# Relay_Board.net
KiCad netlist of a schematic drawn in EAGLE
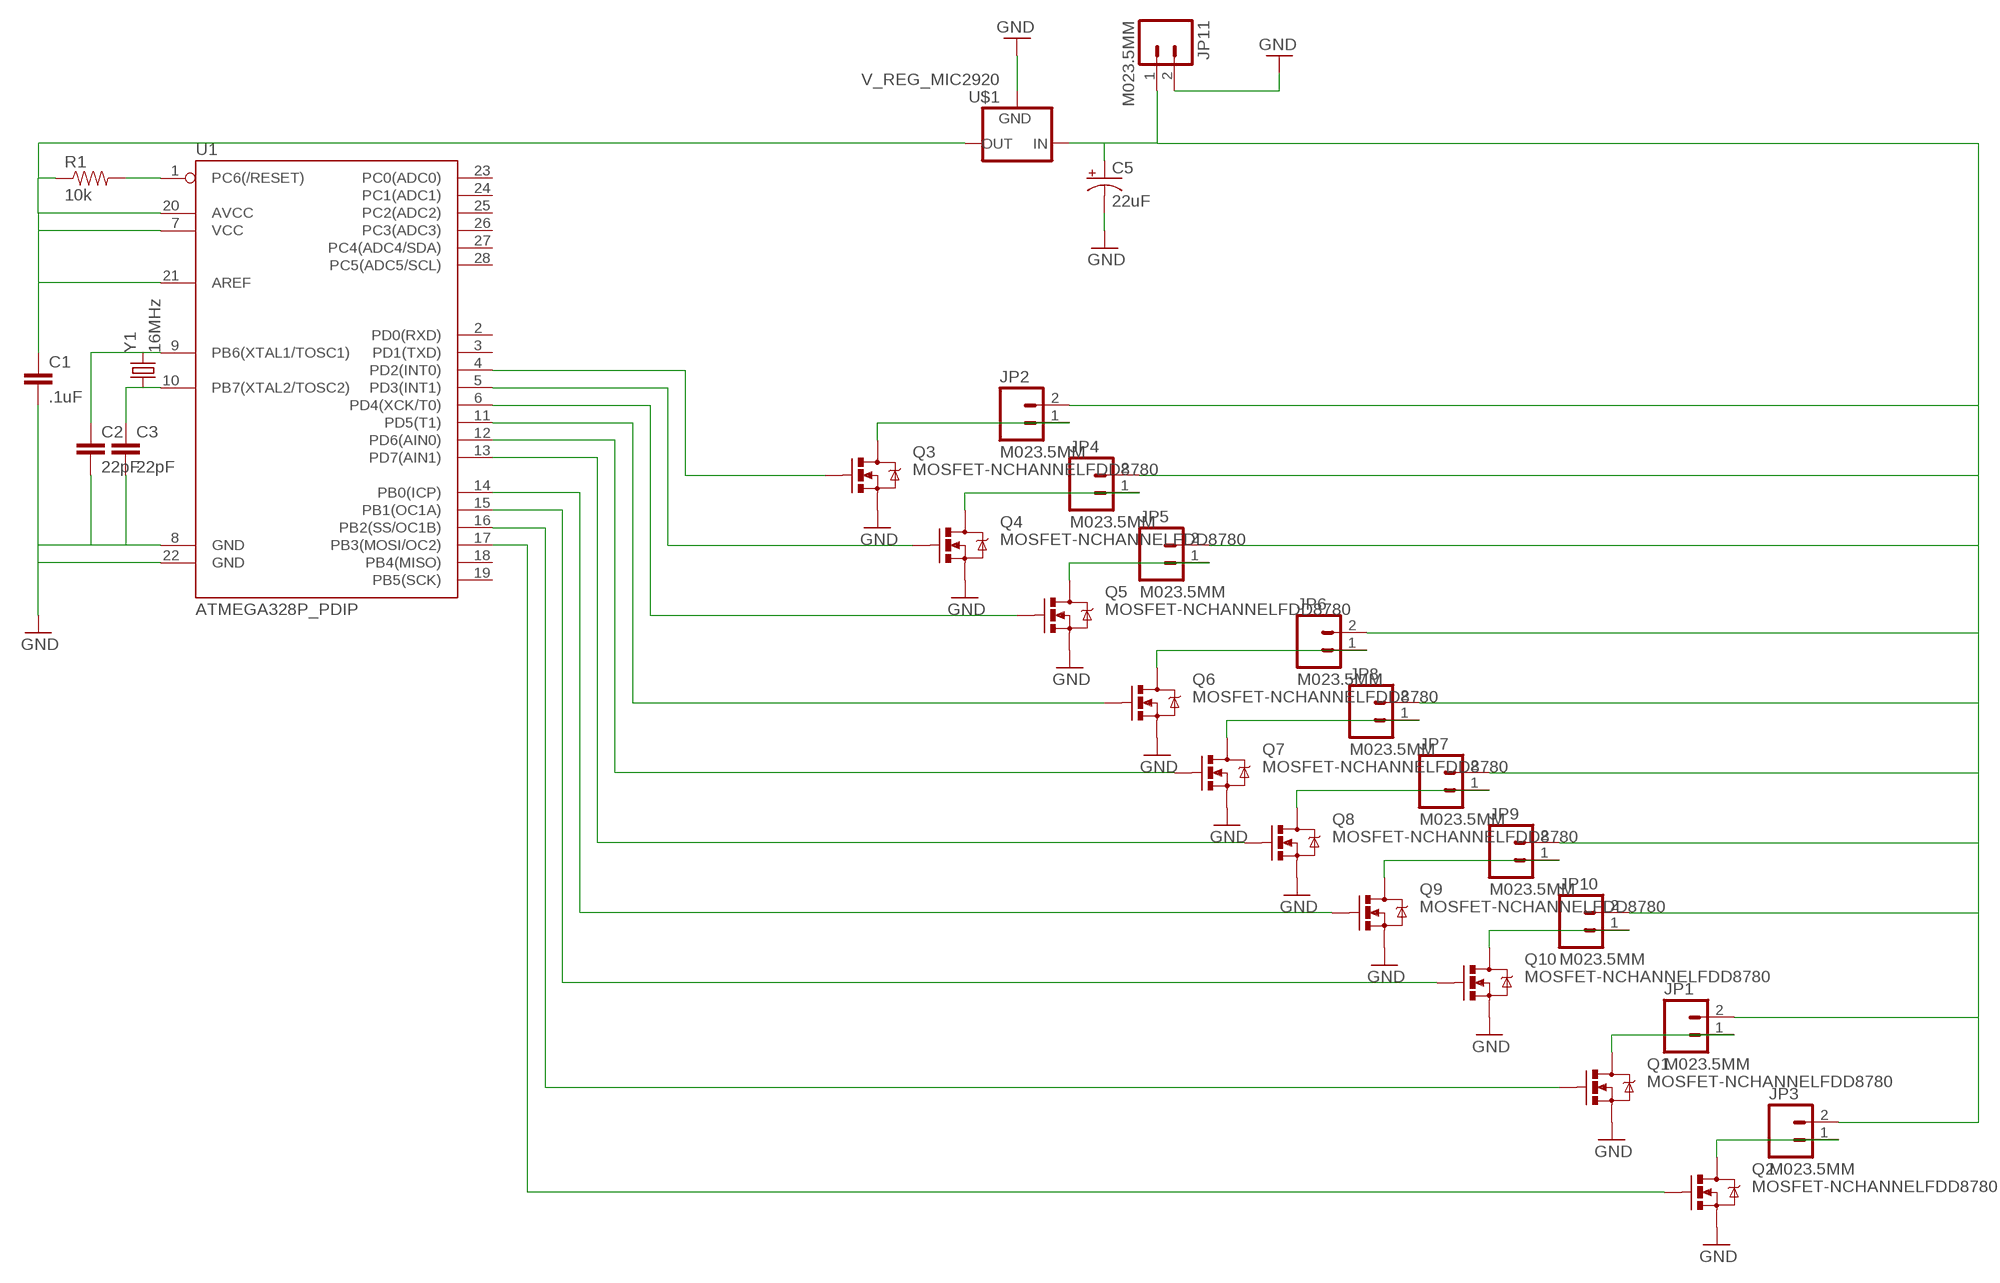
[diagram p0: schematic, sheet 1]

(export (version "E")
  (design (tool "Eeschema 10.0.6"))
  (components
    (comp (ref "C1")
      (value ".1uF")
      (footprint "eagle-import:1206")
      (libsource (lib "eagle-import") (part "CAP1206"))
    )
    (comp (ref "C2")
      (value "22pF")
      (footprint "eagle-import:1206")
      (libsource (lib "eagle-import") (part "CAP1206"))
    )
    (comp (ref "C3")
      (value "22pF")
      (footprint "eagle-import:1206")
      (libsource (lib "eagle-import") (part "CAP1206"))
    )
    (comp (ref "C5")
      (value "22uF")
      (footprint "eagle-import:PANASONIC_C")
      (libsource (lib "eagle-import") (part "CAP_POLC"))
    )
    (comp (ref "JP1")
      (value "M023.5MM")
      (footprint "eagle-import:SCREWTERMINAL-3.5MM-2")
      (libsource (lib "eagle-import") (part "M023.5MM"))
    )
    (comp (ref "JP2")
      (value "M023.5MM")
      (footprint "eagle-import:SCREWTERMINAL-3.5MM-2")
      (libsource (lib "eagle-import") (part "M023.5MM"))
    )
    (comp (ref "JP3")
      (value "M023.5MM")
      (footprint "eagle-import:SCREWTERMINAL-3.5MM-2")
      (libsource (lib "eagle-import") (part "M023.5MM"))
    )
    (comp (ref "JP4")
      (value "M023.5MM")
      (footprint "eagle-import:SCREWTERMINAL-3.5MM-2")
      (libsource (lib "eagle-import") (part "M023.5MM"))
    )
    (comp (ref "JP5")
      (value "M023.5MM")
      (footprint "eagle-import:SCREWTERMINAL-3.5MM-2")
      (libsource (lib "eagle-import") (part "M023.5MM"))
    )
    (comp (ref "JP6")
      (value "M023.5MM")
      (footprint "eagle-import:SCREWTERMINAL-3.5MM-2")
      (libsource (lib "eagle-import") (part "M023.5MM"))
    )
    (comp (ref "JP7")
      (value "M023.5MM")
      (footprint "eagle-import:SCREWTERMINAL-3.5MM-2")
      (libsource (lib "eagle-import") (part "M023.5MM"))
    )
    (comp (ref "JP8")
      (value "M023.5MM")
      (footprint "eagle-import:SCREWTERMINAL-3.5MM-2")
      (libsource (lib "eagle-import") (part "M023.5MM"))
    )
    (comp (ref "JP9")
      (value "M023.5MM")
      (footprint "eagle-import:SCREWTERMINAL-3.5MM-2")
      (libsource (lib "eagle-import") (part "M023.5MM"))
    )
    (comp (ref "JP10")
      (value "M023.5MM")
      (footprint "eagle-import:SCREWTERMINAL-3.5MM-2")
      (libsource (lib "eagle-import") (part "M023.5MM"))
    )
    (comp (ref "JP11")
      (value "M023.5MM")
      (footprint "eagle-import:SCREWTERMINAL-3.5MM-2")
      (libsource (lib "eagle-import") (part "M023.5MM"))
    )
    (comp (ref "Q1")
      (value "MOSFET-NCHANNELFDD8780")
      (footprint "eagle-import:DPAK")
      (libsource (lib "eagle-import") (part "MOSFET-NCHANNELFDD8780"))
    )
    (comp (ref "Q2")
      (value "MOSFET-NCHANNELFDD8780")
      (footprint "eagle-import:DPAK")
      (libsource (lib "eagle-import") (part "MOSFET-NCHANNELFDD8780"))
    )
    (comp (ref "Q3")
      (value "MOSFET-NCHANNELFDD8780")
      (footprint "eagle-import:DPAK")
      (libsource (lib "eagle-import") (part "MOSFET-NCHANNELFDD8780"))
    )
    (comp (ref "Q4")
      (value "MOSFET-NCHANNELFDD8780")
      (footprint "eagle-import:DPAK")
      (libsource (lib "eagle-import") (part "MOSFET-NCHANNELFDD8780"))
    )
    (comp (ref "Q5")
      (value "MOSFET-NCHANNELFDD8780")
      (footprint "eagle-import:DPAK")
      (libsource (lib "eagle-import") (part "MOSFET-NCHANNELFDD8780"))
    )
    (comp (ref "Q6")
      (value "MOSFET-NCHANNELFDD8780")
      (footprint "eagle-import:DPAK")
      (libsource (lib "eagle-import") (part "MOSFET-NCHANNELFDD8780"))
    )
    (comp (ref "Q7")
      (value "MOSFET-NCHANNELFDD8780")
      (footprint "eagle-import:DPAK")
      (libsource (lib "eagle-import") (part "MOSFET-NCHANNELFDD8780"))
    )
    (comp (ref "Q8")
      (value "MOSFET-NCHANNELFDD8780")
      (footprint "eagle-import:DPAK")
      (libsource (lib "eagle-import") (part "MOSFET-NCHANNELFDD8780"))
    )
    (comp (ref "Q9")
      (value "MOSFET-NCHANNELFDD8780")
      (footprint "eagle-import:DPAK")
      (libsource (lib "eagle-import") (part "MOSFET-NCHANNELFDD8780"))
    )
    (comp (ref "Q10")
      (value "MOSFET-NCHANNELFDD8780")
      (footprint "eagle-import:DPAK")
      (libsource (lib "eagle-import") (part "MOSFET-NCHANNELFDD8780"))
    )
    (comp (ref "R1")
      (value "10k")
      (footprint "eagle-import:1206")
      (libsource (lib "eagle-import") (part "RESISTOR1206"))
    )
    (comp (ref "U$1")
      (value "V_REG_MIC2920")
      (footprint "eagle-import:SOT223")
      (libsource (lib "eagle-import") (part "V_REG_MIC2920"))
    )
    (comp (ref "U1")
      (value "ATMEGA328P_PDIP")
      (footprint "eagle-import:DIL28-3")
      (libsource (lib "eagle-import") (part "ATMEGA328P_PDIP"))
    )
    (comp (ref "Y1")
      (value "16MHz")
      (footprint "eagle-import:CRYSTAL-SMD-5X3")
      (libsource (lib "eagle-import") (part "CRYSTAL5X3"))
    )
  )
  (nets
    (net (code "1") (name "GND") (class "Default")
      (node (ref "C1") (pin "2") (pinfunction "2_2") (pintype "passive"))
      (node (ref "C2") (pin "2") (pinfunction "2_2") (pintype "passive"))
      (node (ref "C3") (pin "2") (pinfunction "2_2") (pintype "passive"))
      (node (ref "C5") (pin "-") (pinfunction "-_-") (pintype "passive"))
      (node (ref "JP11") (pin "2") (pinfunction "2_2") (pintype "passive"))
      (node (ref "Q1") (pin "3") (pinfunction "S_3") (pintype "passive"))
      (node (ref "Q10") (pin "3") (pinfunction "S_3") (pintype "passive"))
      (node (ref "Q2") (pin "3") (pinfunction "S_3") (pintype "passive"))
      (node (ref "Q3") (pin "3") (pinfunction "S_3") (pintype "passive"))
      (node (ref "Q4") (pin "3") (pinfunction "S_3") (pintype "passive"))
      (node (ref "Q5") (pin "3") (pinfunction "S_3") (pintype "passive"))
      (node (ref "Q6") (pin "3") (pinfunction "S_3") (pintype "passive"))
      (node (ref "Q7") (pin "3") (pinfunction "S_3") (pintype "passive"))
      (node (ref "Q8") (pin "3") (pinfunction "S_3") (pintype "passive"))
      (node (ref "Q9") (pin "3") (pinfunction "S_3") (pintype "passive"))
      (node (ref "U$1") (pin "2") (pinfunction "GND_2") (pintype "input"))
      (node (ref "U1") (pin "22") (pinfunction "GND_22") (pintype "bidirectional"))
      (node (ref "U1") (pin "8") (pinfunction "GND_8") (pintype "bidirectional"))
    )
    (net (code "2") (name "Net-(Q1-D)") (class "Default")
      (node (ref "JP1") (pin "1") (pinfunction "1_1") (pintype "passive"))
      (node (ref "Q1") (pin "4") (pinfunction "D_4") (pintype "passive"))
    )
    (net (code "3") (name "Net-(Q1-G)") (class "Default")
      (node (ref "Q1") (pin "1") (pinfunction "G_1") (pintype "passive"))
      (node (ref "U1") (pin "16") (pinfunction "PB2(SS/OC1B)_16") (pintype "bidirectional"))
    )
    (net (code "4") (name "Net-(Q2-D)") (class "Default")
      (node (ref "JP3") (pin "1") (pinfunction "1_1") (pintype "passive"))
      (node (ref "Q2") (pin "4") (pinfunction "D_4") (pintype "passive"))
    )
    (net (code "5") (name "Net-(Q2-G)") (class "Default")
      (node (ref "Q2") (pin "1") (pinfunction "G_1") (pintype "passive"))
      (node (ref "U1") (pin "17") (pinfunction "PB3(MOSI/OC2)_17") (pintype "bidirectional"))
    )
    (net (code "6") (name "Net-(Q3-D)") (class "Default")
      (node (ref "JP2") (pin "1") (pinfunction "1_1") (pintype "passive"))
      (node (ref "Q3") (pin "4") (pinfunction "D_4") (pintype "passive"))
    )
    (net (code "7") (name "Net-(Q3-G)") (class "Default")
      (node (ref "Q3") (pin "1") (pinfunction "G_1") (pintype "passive"))
      (node (ref "U1") (pin "4") (pinfunction "PD2(INT0)_4") (pintype "bidirectional"))
    )
    (net (code "8") (name "Net-(Q4-D)") (class "Default")
      (node (ref "JP4") (pin "1") (pinfunction "1_1") (pintype "passive"))
      (node (ref "Q4") (pin "4") (pinfunction "D_4") (pintype "passive"))
    )
    (net (code "9") (name "Net-(Q4-G)") (class "Default")
      (node (ref "Q4") (pin "1") (pinfunction "G_1") (pintype "passive"))
      (node (ref "U1") (pin "5") (pinfunction "PD3(INT1)_5") (pintype "bidirectional"))
    )
    (net (code "10") (name "Net-(Q5-D)") (class "Default")
      (node (ref "JP5") (pin "1") (pinfunction "1_1") (pintype "passive"))
      (node (ref "Q5") (pin "4") (pinfunction "D_4") (pintype "passive"))
    )
    (net (code "11") (name "Net-(Q5-G)") (class "Default")
      (node (ref "Q5") (pin "1") (pinfunction "G_1") (pintype "passive"))
      (node (ref "U1") (pin "6") (pinfunction "PD4(XCK/T0)_6") (pintype "bidirectional"))
    )
    (net (code "12") (name "Net-(Q6-D)") (class "Default")
      (node (ref "JP6") (pin "1") (pinfunction "1_1") (pintype "passive"))
      (node (ref "Q6") (pin "4") (pinfunction "D_4") (pintype "passive"))
    )
    (net (code "13") (name "Net-(Q6-G)") (class "Default")
      (node (ref "Q6") (pin "1") (pinfunction "G_1") (pintype "passive"))
      (node (ref "U1") (pin "11") (pinfunction "PD5(T1)_11") (pintype "bidirectional"))
    )
    (net (code "14") (name "Net-(Q7-D)") (class "Default")
      (node (ref "JP8") (pin "1") (pinfunction "1_1") (pintype "passive"))
      (node (ref "Q7") (pin "4") (pinfunction "D_4") (pintype "passive"))
    )
    (net (code "15") (name "Net-(Q7-G)") (class "Default")
      (node (ref "Q7") (pin "1") (pinfunction "G_1") (pintype "passive"))
      (node (ref "U1") (pin "12") (pinfunction "PD6(AIN0)_12") (pintype "bidirectional"))
    )
    (net (code "16") (name "Net-(Q8-D)") (class "Default")
      (node (ref "JP7") (pin "1") (pinfunction "1_1") (pintype "passive"))
      (node (ref "Q8") (pin "4") (pinfunction "D_4") (pintype "passive"))
    )
    (net (code "17") (name "Net-(Q8-G)") (class "Default")
      (node (ref "Q8") (pin "1") (pinfunction "G_1") (pintype "passive"))
      (node (ref "U1") (pin "13") (pinfunction "PD7(AIN1)_13") (pintype "bidirectional"))
    )
    (net (code "18") (name "Net-(Q9-D)") (class "Default")
      (node (ref "JP9") (pin "1") (pinfunction "1_1") (pintype "passive"))
      (node (ref "Q9") (pin "4") (pinfunction "D_4") (pintype "passive"))
    )
    (net (code "19") (name "Net-(Q9-G)") (class "Default")
      (node (ref "Q9") (pin "1") (pinfunction "G_1") (pintype "passive"))
      (node (ref "U1") (pin "14") (pinfunction "PB0(ICP)_14") (pintype "bidirectional"))
    )
    (net (code "20") (name "Net-(Q10-D)") (class "Default")
      (node (ref "JP10") (pin "1") (pinfunction "1_1") (pintype "passive"))
      (node (ref "Q10") (pin "4") (pinfunction "D_4") (pintype "passive"))
    )
    (net (code "21") (name "Net-(Q10-G)") (class "Default")
      (node (ref "Q10") (pin "1") (pinfunction "G_1") (pintype "passive"))
      (node (ref "U1") (pin "15") (pinfunction "PB1(OC1A)_15") (pintype "bidirectional"))
    )
    (net (code "22") (name "Net-(U$1-IN)") (class "Default")
      (node (ref "C5") (pin "+") (pinfunction "+_+") (pintype "passive"))
      (node (ref "JP1") (pin "2") (pinfunction "2_2") (pintype "passive"))
      (node (ref "JP10") (pin "2") (pinfunction "2_2") (pintype "passive"))
      (node (ref "JP11") (pin "1") (pinfunction "1_1") (pintype "passive"))
      (node (ref "JP2") (pin "2") (pinfunction "2_2") (pintype "passive"))
      (node (ref "JP3") (pin "2") (pinfunction "2_2") (pintype "passive"))
      (node (ref "JP4") (pin "2") (pinfunction "2_2") (pintype "passive"))
      (node (ref "JP5") (pin "2") (pinfunction "2_2") (pintype "passive"))
      (node (ref "JP6") (pin "2") (pinfunction "2_2") (pintype "passive"))
      (node (ref "JP7") (pin "2") (pinfunction "2_2") (pintype "passive"))
      (node (ref "JP8") (pin "2") (pinfunction "2_2") (pintype "passive"))
      (node (ref "JP9") (pin "2") (pinfunction "2_2") (pintype "passive"))
      (node (ref "U$1") (pin "1") (pinfunction "IN_1") (pintype "input"))
    )
    (net (code "23") (name "Net-(U$1-OUT)") (class "Default")
      (node (ref "C1") (pin "1") (pinfunction "1_1") (pintype "passive"))
      (node (ref "R1") (pin "1") (pinfunction "1_1") (pintype "passive"))
      (node (ref "U$1") (pin "3") (pinfunction "OUT_3") (pintype "output"))
      (node (ref "U1") (pin "20") (pinfunction "AVCC_20") (pintype "bidirectional"))
      (node (ref "U1") (pin "21") (pinfunction "AREF_21") (pintype "bidirectional"))
      (node (ref "U1") (pin "7") (pinfunction "VCC_7") (pintype "bidirectional"))
    )
    (net (code "24") (name "Net-(U1-PB6(XTAL1{slash}TOSC1))") (class "Default")
      (node (ref "C2") (pin "1") (pinfunction "1_1") (pintype "passive"))
      (node (ref "U1") (pin "9") (pinfunction "PB6(XTAL1/TOSC1)_9") (pintype "bidirectional"))
      (node (ref "Y1") (pin "3") (pinfunction "2_3") (pintype "passive"))
    )
    (net (code "25") (name "Net-(U1-PB7(XTAL2{slash}TOSC2))") (class "Default")
      (node (ref "C3") (pin "1") (pinfunction "1_1") (pintype "passive"))
      (node (ref "U1") (pin "10") (pinfunction "PB7(XTAL2/TOSC2)_10") (pintype "bidirectional"))
      (node (ref "Y1") (pin "1") (pinfunction "1_1") (pintype "passive"))
    )
    (net (code "26") (name "Net-(U1-PC6({slash}RESET))") (class "Default")
      (node (ref "R1") (pin "2") (pinfunction "2_2") (pintype "passive"))
      (node (ref "U1") (pin "1") (pinfunction "PC6(/RESET)_1") (pintype "bidirectional"))
    )
    (net (code "27") (name "unconnected-(U1-PB4(MISO)-Pad18)") (class "Default")
      (node (ref "U1") (pin "18") (pinfunction "PB4(MISO)_18") (pintype "bidirectional"))
    )
    (net (code "28") (name "unconnected-(U1-PB5(SCK)-Pad19)") (class "Default")
      (node (ref "U1") (pin "19") (pinfunction "PB5(SCK)_19") (pintype "bidirectional"))
    )
    (net (code "29") (name "unconnected-(U1-PC0(ADC0)-Pad23)") (class "Default")
      (node (ref "U1") (pin "23") (pinfunction "PC0(ADC0)_23") (pintype "bidirectional"))
    )
    (net (code "30") (name "unconnected-(U1-PC1(ADC1)-Pad24)") (class "Default")
      (node (ref "U1") (pin "24") (pinfunction "PC1(ADC1)_24") (pintype "bidirectional"))
    )
    (net (code "31") (name "unconnected-(U1-PC2(ADC2)-Pad25)") (class "Default")
      (node (ref "U1") (pin "25") (pinfunction "PC2(ADC2)_25") (pintype "bidirectional"))
    )
    (net (code "32") (name "unconnected-(U1-PC3(ADC3)-Pad26)") (class "Default")
      (node (ref "U1") (pin "26") (pinfunction "PC3(ADC3)_26") (pintype "bidirectional"))
    )
    (net (code "33") (name "unconnected-(U1-PC4(ADC4{slash}SDA)-Pad27)") (class "Default")
      (node (ref "U1") (pin "27") (pinfunction "PC4(ADC4/SDA)_27") (pintype "bidirectional"))
    )
    (net (code "34") (name "unconnected-(U1-PC5(ADC5{slash}SCL)-Pad28)") (class "Default")
      (node (ref "U1") (pin "28") (pinfunction "PC5(ADC5/SCL)_28") (pintype "bidirectional"))
    )
    (net (code "35") (name "unconnected-(U1-PD0(RXD)-Pad2)") (class "Default")
      (node (ref "U1") (pin "2") (pinfunction "PD0(RXD)_2") (pintype "bidirectional"))
    )
    (net (code "36") (name "unconnected-(U1-PD1(TXD)-Pad3)") (class "Default")
      (node (ref "U1") (pin "3") (pinfunction "PD1(TXD)_3") (pintype "bidirectional"))
    )
  )
)
